# optocouplers.net
KiCad netlist of a schematic drawn in Altium Designer
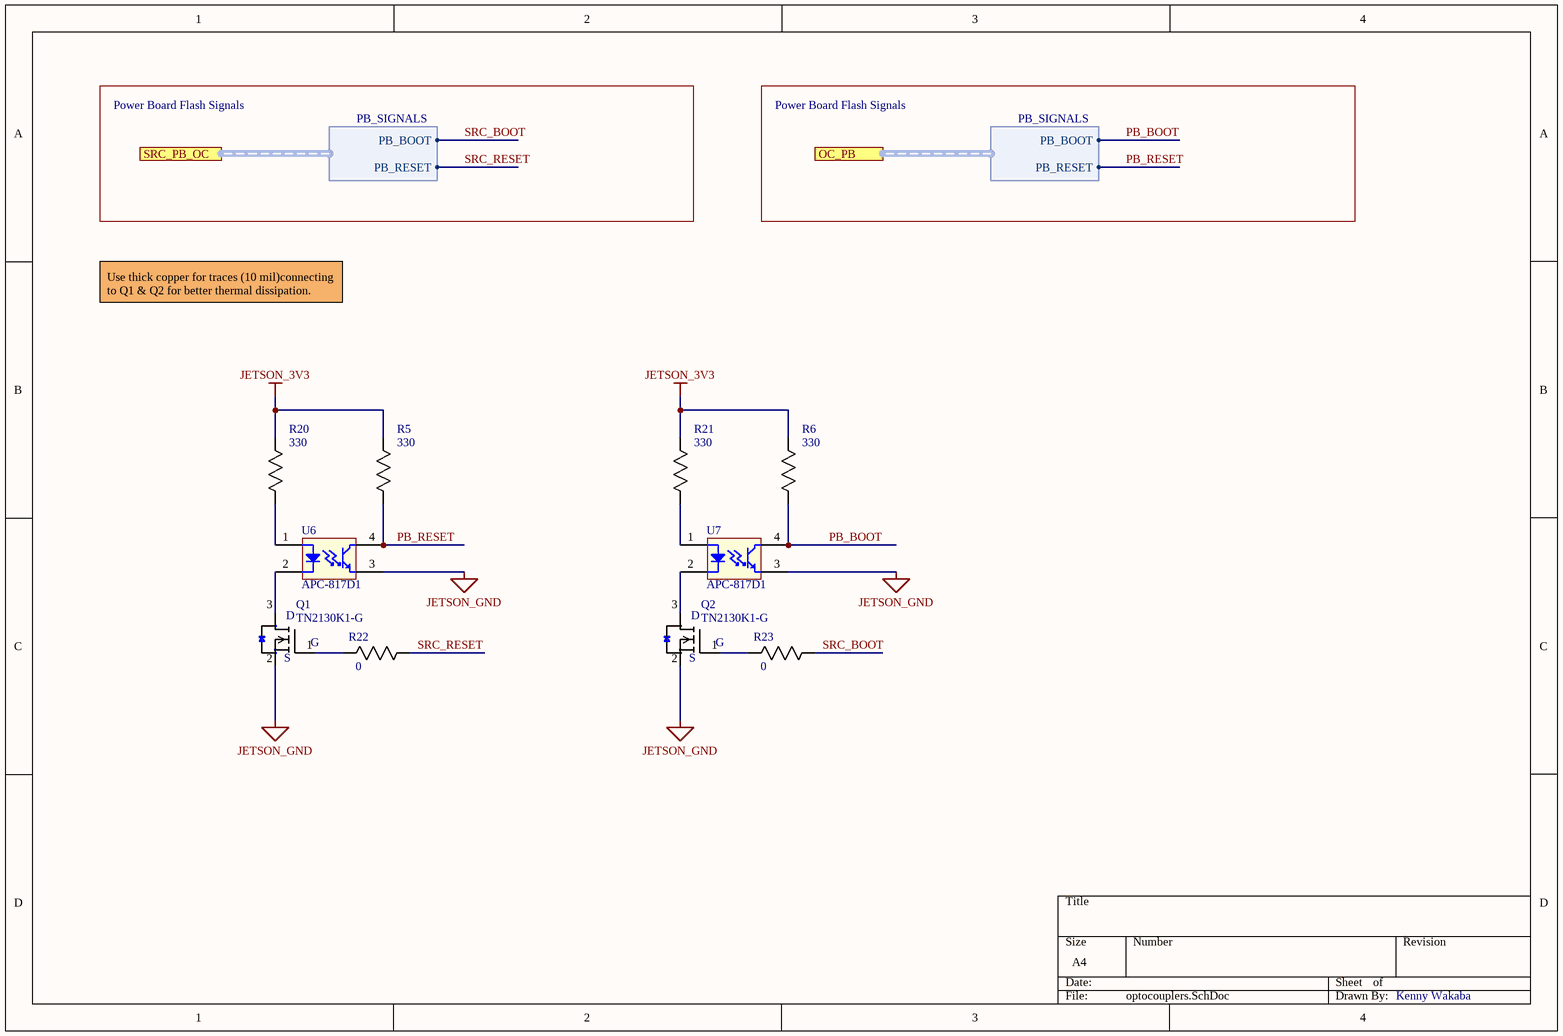
[diagram p0: optocouplers.SchDoc]

(export (version "E")
  (design (tool "Eeschema 10.0.6"))
  (components
    (comp (ref "Q1")
      (value "TN2130K1-G")
      (footprint "SOT95P237X112-3N")
      (description "N-Channel 300 V 85mA (Tj) 360mW (Tc) Surface Mount TO-236AB (SOT23)")
      (fields
        (field (name "PART NUMBER") "MOSFET N-CH TN2130K1-G")
        (field (name "COPYRIGHT") "Copyright (C) 2021 Ultra Librarian. All rights reserved.")
      )
      (libsource (lib "Transistor_Library") (part "MOSFET N-CH TN2130K1-G"))
    )
    (comp (ref "Q2")
      (value "TN2130K1-G")
      (footprint "SOT95P237X112-3N")
      (description "N-Channel 300 V 85mA (Tj) 360mW (Tc) Surface Mount TO-236AB (SOT23)")
      (fields
        (field (name "PART NUMBER") "MOSFET N-CH TN2130K1-G")
        (field (name "COPYRIGHT") "Copyright (C) 2021 Ultra Librarian. All rights reserved.")
      )
      (libsource (lib "Transistor_Library") (part "MOSFET N-CH TN2130K1-G"))
    )
    (comp (ref "R5")
      (value "330")
      (footprint "0603")
      (description "Default Resistor Symbol")
      (fields (field (name "TOLERANCE") "5%") (field (name "PART NUMBER") "RES 330.0 1/8W - 5%"))
      (libsource (lib "Resistor_Library") (part "RES_DEFAULT"))
    )
    (comp (ref "R6")
      (value "330")
      (footprint "0603")
      (description "Default Resistor Symbol")
      (fields (field (name "TOLERANCE") "5%") (field (name "PART NUMBER") "RES 330.0 1/8W - 5%"))
      (libsource (lib "Resistor_Library") (part "RES_DEFAULT"))
    )
    (comp (ref "R20")
      (value "330")
      (footprint "0603")
      (description "Default Resistor Symbol")
      (fields (field (name "TOLERANCE") "5%") (field (name "PART NUMBER") "RES 330.0 1/8W - 5%"))
      (libsource (lib "") (part "RES_DEFAULT_1"))
    )
    (comp (ref "R21")
      (value "330")
      (footprint "0603")
      (description "Default Resistor Symbol")
      (fields (field (name "TOLERANCE") "5%") (field (name "PART NUMBER") "RES 330.0 1/8W - 5%"))
      (libsource (lib "") (part "RES_DEFAULT_1"))
    )
    (comp (ref "R22")
      (value "0")
      (footprint "0603")
      (description "Default Resistor Symbol")
      (fields (field (name "PART NUMBER") "RES 0 JUMPER 0603"))
      (libsource (lib "") (part "RES_DEFAULT_1"))
    )
    (comp (ref "R23")
      (value "0")
      (footprint "0603")
      (description "Default Resistor Symbol")
      (fields (field (name "PART NUMBER") "RES 0 JUMPER 0603"))
      (libsource (lib "") (part "RES_DEFAULT_1"))
    )
    (comp (ref "U6")
      (value "APC-817D1")
      (footprint "APC-817D1")
      (description "DIP4, DC Input, Optocoupler")
      (libsource (lib "IC_Library") (part "APC-817D1"))
    )
    (comp (ref "U7")
      (value "APC-817D1")
      (footprint "APC-817D1")
      (description "DIP4, DC Input, Optocoupler")
      (libsource (lib "IC_Library") (part "APC-817D1"))
    )
  )
  (nets
    (net (code "2") (name "/PB_BOOT") (class "Default")
      (node (ref "R6") (pin "1") (pinfunction "R1_1") (pintype "passive"))
      (node (ref "U7") (pin "4") (pinfunction "4_4") (pintype "passive"))
    )
    (net (code "3") (name "/PB_RESET") (class "Default")
      (node (ref "R5") (pin "1") (pinfunction "R1_1") (pintype "passive"))
      (node (ref "U6") (pin "4") (pinfunction "4_4") (pintype "passive"))
    )
    (net (code "4") (name "/SRC_BOOT") (class "Default")
      (node (ref "R23") (pin "1") (pinfunction "R1_1") (pintype "passive"))
    )
    (net (code "5") (name "/SRC_RESET") (class "Default")
      (node (ref "R22") (pin "1") (pinfunction "R1_1") (pintype "passive"))
    )
    (net (code "7") (name "JETSON_3V3") (class "Default")
      (node (ref "R20") (pin "2") (pinfunction "R2_2") (pintype "passive"))
      (node (ref "R21") (pin "2") (pinfunction "R2_2") (pintype "passive"))
      (node (ref "R5") (pin "2") (pinfunction "R2_2") (pintype "passive"))
      (node (ref "R6") (pin "2") (pinfunction "R2_2") (pintype "passive"))
    )
    (net (code "8") (name "JETSON_GND") (class "Default")
      (node (ref "Q1") (pin "2") (pinfunction "S_2") (pintype "passive"))
      (node (ref "Q2") (pin "2") (pinfunction "S_2") (pintype "passive"))
      (node (ref "U6") (pin "3") (pinfunction "3_3") (pintype "passive"))
      (node (ref "U7") (pin "3") (pinfunction "3_3") (pintype "passive"))
    )
    (net (code "9") (name "Net-(Q1-D)") (class "Default")
      (node (ref "Q1") (pin "3") (pinfunction "D_3") (pintype "passive"))
      (node (ref "U6") (pin "2") (pinfunction "2_2") (pintype "passive"))
    )
    (net (code "10") (name "Net-(Q1-G)") (class "Default")
      (node (ref "Q1") (pin "1") (pinfunction "G_1") (pintype "passive"))
      (node (ref "R22") (pin "2") (pinfunction "R2_2") (pintype "passive"))
    )
    (net (code "11") (name "Net-(Q2-D)") (class "Default")
      (node (ref "Q2") (pin "3") (pinfunction "D_3") (pintype "passive"))
      (node (ref "U7") (pin "2") (pinfunction "2_2") (pintype "passive"))
    )
    (net (code "12") (name "Net-(Q2-G)") (class "Default")
      (node (ref "Q2") (pin "1") (pinfunction "G_1") (pintype "passive"))
      (node (ref "R23") (pin "2") (pinfunction "R2_2") (pintype "passive"))
    )
    (net (code "13") (name "Net-(R20-R1)") (class "Default")
      (node (ref "R20") (pin "1") (pinfunction "R1_1") (pintype "passive"))
      (node (ref "U6") (pin "1") (pinfunction "1_1") (pintype "passive"))
    )
    (net (code "14") (name "Net-(R21-R1)") (class "Default")
      (node (ref "R21") (pin "1") (pinfunction "R1_1") (pintype "passive"))
      (node (ref "U7") (pin "1") (pinfunction "1_1") (pintype "passive"))
    )
  )
)
